# ina_board.net
KiCad netlist of a schematic drawn in EAGLE
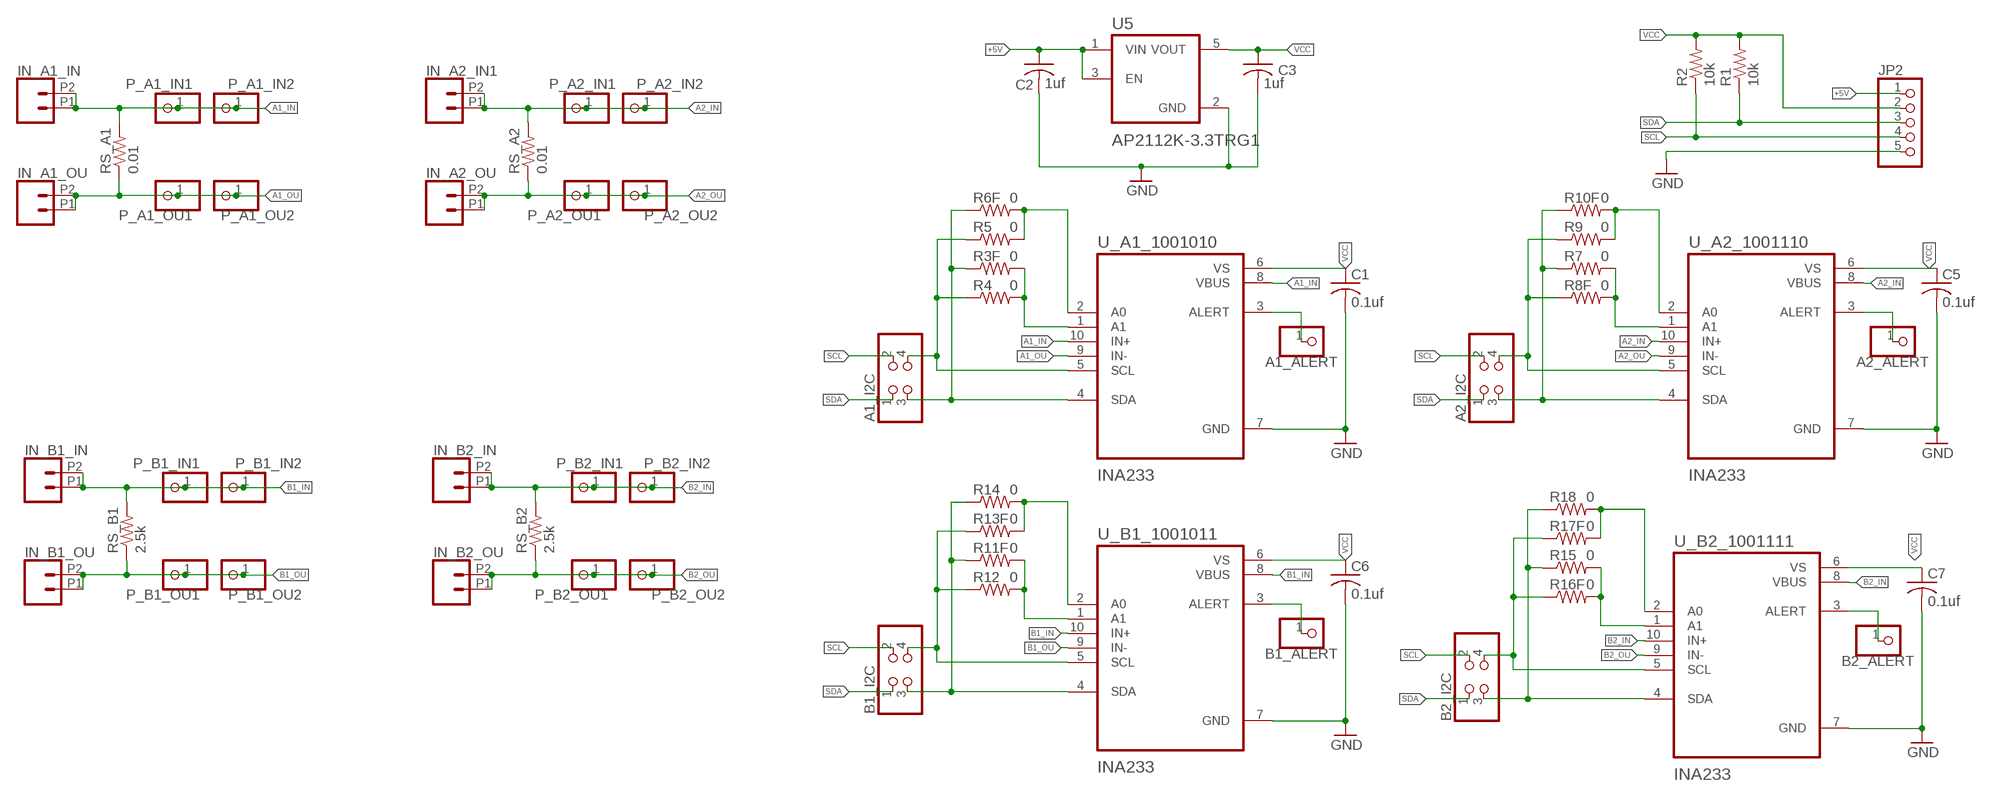
[diagram p0: schematic, sheet 1]

(export (version "E")
  (design (tool "Eeschema 10.0.6"))
  (components
    (comp (ref "A1_ALERT")
      (value "PINHD-1X1")
      (footprint "eagle-import:1X01")
      (libsource (lib "eagle-import") (part "pinhead_325_PINHD-1X1"))
    )
    (comp (ref "A1_I2C")
      (value "PINHD-2X2")
      (footprint "eagle-import:2X02")
      (libsource (lib "eagle-import") (part "PINHD-2X2"))
    )
    (comp (ref "A2_ALERT")
      (value "PINHD-1X1")
      (footprint "eagle-import:1X01")
      (libsource (lib "eagle-import") (part "pinhead_325_PINHD-1X1"))
    )
    (comp (ref "A2_I2C")
      (value "PINHD-2X2")
      (footprint "eagle-import:2X02")
      (libsource (lib "eagle-import") (part "PINHD-2X2"))
    )
    (comp (ref "B1_ALERT")
      (value "PINHD-1X1")
      (footprint "eagle-import:1X01")
      (libsource (lib "eagle-import") (part "pinhead_325_PINHD-1X1"))
    )
    (comp (ref "B1_I2C")
      (value "PINHD-2X2")
      (footprint "eagle-import:2X02")
      (libsource (lib "eagle-import") (part "PINHD-2X2"))
    )
    (comp (ref "B2_ALERT")
      (value "PINHD-1X1")
      (footprint "eagle-import:1X01")
      (libsource (lib "eagle-import") (part "pinhead_325_PINHD-1X1"))
    )
    (comp (ref "B2_I2C")
      (value "PINHD-2X2")
      (footprint "eagle-import:2X02")
      (libsource (lib "eagle-import") (part "PINHD-2X2"))
    )
    (comp (ref "C1")
      (value "0.1uf")
      (footprint "eagle-import:C0805")
      (libsource (lib "eagle-import") (part "C-USC0805"))
    )
    (comp (ref "C2")
      (value "1uf")
      (footprint "eagle-import:C1210")
      (libsource (lib "eagle-import") (part "C-USC1210"))
    )
    (comp (ref "C3")
      (value "1uf")
      (footprint "eagle-import:C1210")
      (libsource (lib "eagle-import") (part "C-USC1210"))
    )
    (comp (ref "C5")
      (value "0.1uf")
      (footprint "eagle-import:C0805")
      (libsource (lib "eagle-import") (part "C-USC0805"))
    )
    (comp (ref "C6")
      (value "0.1uf")
      (footprint "eagle-import:C0805")
      (libsource (lib "eagle-import") (part "C-USC0805"))
    )
    (comp (ref "C7")
      (value "0.1uf")
      (footprint "eagle-import:C0805")
      (libsource (lib "eagle-import") (part "C-USC0805"))
    )
    (comp (ref "IN_A1_IN")
      (value "CONN_022.54MM_SCREWTERM")
      (footprint "eagle-import:1X02_2.54_SCREWTERM")
      (libsource (lib "eagle-import") (part "CONN_022.54MM_SCREWTERM"))
    )
    (comp (ref "IN_A1_OU")
      (value "CONN_022.54MM_SCREWTERM")
      (footprint "eagle-import:1X02_2.54_SCREWTERM")
      (libsource (lib "eagle-import") (part "CONN_022.54MM_SCREWTERM"))
    )
    (comp (ref "IN_A2_IN1")
      (value "CONN_022.54MM_SCREWTERM")
      (footprint "eagle-import:1X02_2.54_SCREWTERM")
      (libsource (lib "eagle-import") (part "CONN_022.54MM_SCREWTERM"))
    )
    (comp (ref "IN_A2_OU")
      (value "CONN_022.54MM_SCREWTERM")
      (footprint "eagle-import:1X02_2.54_SCREWTERM")
      (libsource (lib "eagle-import") (part "CONN_022.54MM_SCREWTERM"))
    )
    (comp (ref "IN_B1_IN")
      (value "CONN_022.54MM_SCREWTERM")
      (footprint "eagle-import:1X02_2.54_SCREWTERM")
      (libsource (lib "eagle-import") (part "CONN_022.54MM_SCREWTERM"))
    )
    (comp (ref "IN_B1_OU")
      (value "CONN_022.54MM_SCREWTERM")
      (footprint "eagle-import:1X02_2.54_SCREWTERM")
      (libsource (lib "eagle-import") (part "CONN_022.54MM_SCREWTERM"))
    )
    (comp (ref "IN_B2_IN")
      (value "CONN_022.54MM_SCREWTERM")
      (footprint "eagle-import:1X02_2.54_SCREWTERM")
      (libsource (lib "eagle-import") (part "CONN_022.54MM_SCREWTERM"))
    )
    (comp (ref "IN_B2_OU")
      (value "CONN_022.54MM_SCREWTERM")
      (footprint "eagle-import:1X02_2.54_SCREWTERM")
      (libsource (lib "eagle-import") (part "CONN_022.54MM_SCREWTERM"))
    )
    (comp (ref "JP2")
      (value "PINHD-1X5")
      (footprint "eagle-import:1X05")
      (libsource (lib "eagle-import") (part "PINHD-1X5"))
    )
    (comp (ref "P_A1_IN1")
      (value "PINHD-1X1")
      (footprint "eagle-import:1X01")
      (libsource (lib "eagle-import") (part "PINHD-1X1"))
    )
    (comp (ref "P_A1_IN2")
      (value "PINHD-1X1")
      (footprint "eagle-import:1X01")
      (libsource (lib "eagle-import") (part "PINHD-1X1"))
    )
    (comp (ref "P_A1_OU1")
      (value "PINHD-1X1")
      (footprint "eagle-import:1X01")
      (libsource (lib "eagle-import") (part "PINHD-1X1"))
    )
    (comp (ref "P_A1_OU2")
      (value "PINHD-1X1")
      (footprint "eagle-import:1X01")
      (libsource (lib "eagle-import") (part "PINHD-1X1"))
    )
    (comp (ref "P_A2_IN1")
      (value "PINHD-1X1")
      (footprint "eagle-import:1X01")
      (libsource (lib "eagle-import") (part "PINHD-1X1"))
    )
    (comp (ref "P_A2_IN2")
      (value "PINHD-1X1")
      (footprint "eagle-import:1X01")
      (libsource (lib "eagle-import") (part "PINHD-1X1"))
    )
    (comp (ref "P_A2_OU1")
      (value "PINHD-1X1")
      (footprint "eagle-import:1X01")
      (libsource (lib "eagle-import") (part "PINHD-1X1"))
    )
    (comp (ref "P_A2_OU2")
      (value "PINHD-1X1")
      (footprint "eagle-import:1X01")
      (libsource (lib "eagle-import") (part "PINHD-1X1"))
    )
    (comp (ref "P_B1_IN1")
      (value "PINHD-1X1")
      (footprint "eagle-import:1X01")
      (libsource (lib "eagle-import") (part "PINHD-1X1"))
    )
    (comp (ref "P_B1_IN2")
      (value "PINHD-1X1")
      (footprint "eagle-import:1X01")
      (libsource (lib "eagle-import") (part "PINHD-1X1"))
    )
    (comp (ref "P_B1_OU1")
      (value "PINHD-1X1")
      (footprint "eagle-import:1X01")
      (libsource (lib "eagle-import") (part "PINHD-1X1"))
    )
    (comp (ref "P_B1_OU2")
      (value "PINHD-1X1")
      (footprint "eagle-import:1X01")
      (libsource (lib "eagle-import") (part "PINHD-1X1"))
    )
    (comp (ref "P_B2_IN1")
      (value "PINHD-1X1")
      (footprint "eagle-import:1X01")
      (libsource (lib "eagle-import") (part "PINHD-1X1"))
    )
    (comp (ref "P_B2_IN2")
      (value "PINHD-1X1")
      (footprint "eagle-import:1X01")
      (libsource (lib "eagle-import") (part "PINHD-1X1"))
    )
    (comp (ref "P_B2_OU1")
      (value "PINHD-1X1")
      (footprint "eagle-import:1X01")
      (libsource (lib "eagle-import") (part "PINHD-1X1"))
    )
    (comp (ref "P_B2_OU2")
      (value "PINHD-1X1")
      (footprint "eagle-import:1X01")
      (libsource (lib "eagle-import") (part "PINHD-1X1"))
    )
    (comp (ref "R1")
      (value "10k")
      (footprint "eagle-import:R0805")
      (libsource (lib "eagle-import") (part "R-US_R0805"))
    )
    (comp (ref "R2")
      (value "10k")
      (footprint "eagle-import:R0805")
      (libsource (lib "eagle-import") (part "R-US_R0805"))
    )
    (comp (ref "R3F")
      (value "0")
      (footprint "eagle-import:R0805")
      (libsource (lib "eagle-import") (part "R-US_R0805"))
    )
    (comp (ref "R4")
      (value "0")
      (footprint "eagle-import:R0805")
      (libsource (lib "eagle-import") (part "R-US_R0805"))
    )
    (comp (ref "R5")
      (value "0")
      (footprint "eagle-import:R0805")
      (libsource (lib "eagle-import") (part "R-US_R0805"))
    )
    (comp (ref "R6F")
      (value "0")
      (footprint "eagle-import:R0805")
      (libsource (lib "eagle-import") (part "R-US_R0805"))
    )
    (comp (ref "R7")
      (value "0")
      (footprint "eagle-import:R0805")
      (libsource (lib "eagle-import") (part "R-US_R0805"))
    )
    (comp (ref "R8F")
      (value "0")
      (footprint "eagle-import:R0805")
      (libsource (lib "eagle-import") (part "R-US_R0805"))
    )
    (comp (ref "R9")
      (value "0")
      (footprint "eagle-import:R0805")
      (libsource (lib "eagle-import") (part "R-US_R0805"))
    )
    (comp (ref "R10F")
      (value "0")
      (footprint "eagle-import:R0805")
      (libsource (lib "eagle-import") (part "R-US_R0805"))
    )
    (comp (ref "R11F")
      (value "0")
      (footprint "eagle-import:R0805")
      (libsource (lib "eagle-import") (part "R-US_R0805"))
    )
    (comp (ref "R12")
      (value "0")
      (footprint "eagle-import:R0805")
      (libsource (lib "eagle-import") (part "R-US_R0805"))
    )
    (comp (ref "R13F")
      (value "0")
      (footprint "eagle-import:R0805")
      (libsource (lib "eagle-import") (part "R-US_R0805"))
    )
    (comp (ref "R14")
      (value "0")
      (footprint "eagle-import:R0805")
      (libsource (lib "eagle-import") (part "R-US_R0805"))
    )
    (comp (ref "R15")
      (value "0")
      (footprint "eagle-import:R0805")
      (libsource (lib "eagle-import") (part "R-US_R0805"))
    )
    (comp (ref "R16F")
      (value "0")
      (footprint "eagle-import:R0805")
      (libsource (lib "eagle-import") (part "R-US_R0805"))
    )
    (comp (ref "R17F")
      (value "0")
      (footprint "eagle-import:R0805")
      (libsource (lib "eagle-import") (part "R-US_R0805"))
    )
    (comp (ref "R18")
      (value "0")
      (footprint "eagle-import:R0805")
      (libsource (lib "eagle-import") (part "R-US_R0805"))
    )
    (comp (ref "RS_A1")
      (value "0.01")
      (footprint "eagle-import:R2512")
      (libsource (lib "eagle-import") (part "R-US_R2512"))
    )
    (comp (ref "RS_A2")
      (value "0.01")
      (footprint "eagle-import:R2512")
      (libsource (lib "eagle-import") (part "R-US_R2512"))
    )
    (comp (ref "RS_B1")
      (value "2.5k")
      (footprint "eagle-import:R0805")
      (libsource (lib "eagle-import") (part "R-US_R0805"))
    )
    (comp (ref "RS_B2")
      (value "2.5k")
      (footprint "eagle-import:R0805")
      (libsource (lib "eagle-import") (part "R-US_R0805"))
    )
    (comp (ref "U5")
      (value "AP2112K-3.3TRG1")
      (footprint "eagle-import:SOT95P285X140-5N")
      (fields (field (name "MF") "Diodes Inc."))
      (libsource (lib "eagle-import") (part "AP2112K-3.3TRG1"))
    )
    (comp (ref "U_A1_1001010")
      (value "INA233")
      (footprint "eagle-import:SOP50P490X110-10N")
      (fields (field (name "MF") "Texas Instruments") (field (name "MP") "INA226AIDGST"))
      (libsource (lib "eagle-import") (part "INA226AIDGST"))
    )
    (comp (ref "U_A2_1001110")
      (value "INA233")
      (footprint "eagle-import:SOP50P490X110-10N")
      (fields (field (name "MF") "Texas Instruments") (field (name "MP") "INA226AIDGST"))
      (libsource (lib "eagle-import") (part "INA226AIDGST"))
    )
    (comp (ref "U_B1_1001011")
      (value "INA233")
      (footprint "eagle-import:SOP50P490X110-10N")
      (fields (field (name "MF") "Texas Instruments") (field (name "MP") "INA226AIDGST"))
      (libsource (lib "eagle-import") (part "INA226AIDGST"))
    )
    (comp (ref "U_B2_1001111")
      (value "INA233")
      (footprint "eagle-import:SOP50P490X110-10N")
      (fields (field (name "MF") "Texas Instruments") (field (name "MP") "INA226AIDGST"))
      (libsource (lib "eagle-import") (part "INA226AIDGST"))
    )
  )
  (nets
    (net (code "1") (name "+5V") (class "Default")
      (node (ref "C2") (pin "1") (pinfunction "1_1") (pintype "passive"))
      (node (ref "JP2") (pin "1") (pinfunction "1_1") (pintype "passive"))
      (node (ref "U5") (pin "1") (pinfunction "VIN_1") (pintype "power_in"))
      (node (ref "U5") (pin "3") (pinfunction "EN_3") (pintype "input"))
    )
    (net (code "2") (name "A1_IN") (class "Default")
      (node (ref "IN_A1_IN") (pin "P1") (pinfunction "1_P1") (pintype "passive"))
      (node (ref "IN_A1_IN") (pin "P2") (pinfunction "2_P2") (pintype "passive"))
      (node (ref "P_A1_IN1") (pin "1") (pinfunction "1_1") (pintype "passive"))
      (node (ref "P_A1_IN2") (pin "1") (pinfunction "1_1") (pintype "passive"))
      (node (ref "RS_A1") (pin "2") (pinfunction "2_2") (pintype "passive"))
      (node (ref "U_A1_1001010") (pin "10") (pinfunction "IN+_10") (pintype "input"))
      (node (ref "U_A1_1001010") (pin "8") (pinfunction "VBUS_8") (pintype "power_in"))
    )
    (net (code "3") (name "A1_OU") (class "Default")
      (node (ref "IN_A1_OU") (pin "P1") (pinfunction "1_P1") (pintype "passive"))
      (node (ref "IN_A1_OU") (pin "P2") (pinfunction "2_P2") (pintype "passive"))
      (node (ref "P_A1_OU1") (pin "1") (pinfunction "1_1") (pintype "passive"))
      (node (ref "P_A1_OU2") (pin "1") (pinfunction "1_1") (pintype "passive"))
      (node (ref "RS_A1") (pin "1") (pinfunction "1_1") (pintype "passive"))
      (node (ref "U_A1_1001010") (pin "9") (pinfunction "IN-_9") (pintype "input"))
    )
    (net (code "4") (name "A2_IN") (class "Default")
      (node (ref "IN_A2_IN1") (pin "P1") (pinfunction "1_P1") (pintype "passive"))
      (node (ref "IN_A2_IN1") (pin "P2") (pinfunction "2_P2") (pintype "passive"))
      (node (ref "P_A2_IN1") (pin "1") (pinfunction "1_1") (pintype "passive"))
      (node (ref "P_A2_IN2") (pin "1") (pinfunction "1_1") (pintype "passive"))
      (node (ref "RS_A2") (pin "2") (pinfunction "2_2") (pintype "passive"))
      (node (ref "U_A2_1001110") (pin "10") (pinfunction "IN+_10") (pintype "input"))
      (node (ref "U_A2_1001110") (pin "8") (pinfunction "VBUS_8") (pintype "power_in"))
    )
    (net (code "5") (name "A2_OU") (class "Default")
      (node (ref "IN_A2_OU") (pin "P1") (pinfunction "1_P1") (pintype "passive"))
      (node (ref "IN_A2_OU") (pin "P2") (pinfunction "2_P2") (pintype "passive"))
      (node (ref "P_A2_OU1") (pin "1") (pinfunction "1_1") (pintype "passive"))
      (node (ref "P_A2_OU2") (pin "1") (pinfunction "1_1") (pintype "passive"))
      (node (ref "RS_A2") (pin "1") (pinfunction "1_1") (pintype "passive"))
      (node (ref "U_A2_1001110") (pin "9") (pinfunction "IN-_9") (pintype "input"))
    )
    (net (code "6") (name "B1_IN") (class "Default")
      (node (ref "IN_B1_IN") (pin "P1") (pinfunction "1_P1") (pintype "passive"))
      (node (ref "IN_B1_IN") (pin "P2") (pinfunction "2_P2") (pintype "passive"))
      (node (ref "P_B1_IN1") (pin "1") (pinfunction "1_1") (pintype "passive"))
      (node (ref "P_B1_IN2") (pin "1") (pinfunction "1_1") (pintype "passive"))
      (node (ref "RS_B1") (pin "2") (pinfunction "2_2") (pintype "passive"))
      (node (ref "U_B1_1001011") (pin "10") (pinfunction "IN+_10") (pintype "input"))
      (node (ref "U_B1_1001011") (pin "8") (pinfunction "VBUS_8") (pintype "power_in"))
    )
    (net (code "7") (name "B1_OU") (class "Default")
      (node (ref "IN_B1_OU") (pin "P1") (pinfunction "1_P1") (pintype "passive"))
      (node (ref "IN_B1_OU") (pin "P2") (pinfunction "2_P2") (pintype "passive"))
      (node (ref "P_B1_OU1") (pin "1") (pinfunction "1_1") (pintype "passive"))
      (node (ref "P_B1_OU2") (pin "1") (pinfunction "1_1") (pintype "passive"))
      (node (ref "RS_B1") (pin "1") (pinfunction "1_1") (pintype "passive"))
      (node (ref "U_B1_1001011") (pin "9") (pinfunction "IN-_9") (pintype "input"))
    )
    (net (code "8") (name "B2_IN") (class "Default")
      (node (ref "IN_B2_IN") (pin "P1") (pinfunction "1_P1") (pintype "passive"))
      (node (ref "IN_B2_IN") (pin "P2") (pinfunction "2_P2") (pintype "passive"))
      (node (ref "P_B2_IN1") (pin "1") (pinfunction "1_1") (pintype "passive"))
      (node (ref "P_B2_IN2") (pin "1") (pinfunction "1_1") (pintype "passive"))
      (node (ref "RS_B2") (pin "2") (pinfunction "2_2") (pintype "passive"))
      (node (ref "U_B2_1001111") (pin "10") (pinfunction "IN+_10") (pintype "input"))
      (node (ref "U_B2_1001111") (pin "8") (pinfunction "VBUS_8") (pintype "power_in"))
    )
    (net (code "9") (name "B2_OU") (class "Default")
      (node (ref "IN_B2_OU") (pin "P1") (pinfunction "1_P1") (pintype "passive"))
      (node (ref "IN_B2_OU") (pin "P2") (pinfunction "2_P2") (pintype "passive"))
      (node (ref "P_B2_OU1") (pin "1") (pinfunction "1_1") (pintype "passive"))
      (node (ref "P_B2_OU2") (pin "1") (pinfunction "1_1") (pintype "passive"))
      (node (ref "RS_B2") (pin "1") (pinfunction "1_1") (pintype "passive"))
      (node (ref "U_B2_1001111") (pin "9") (pinfunction "IN-_9") (pintype "input"))
    )
    (net (code "10") (name "GND") (class "Default")
      (node (ref "C1") (pin "2") (pinfunction "2_2") (pintype "passive"))
      (node (ref "C2") (pin "2") (pinfunction "2_2") (pintype "passive"))
      (node (ref "C3") (pin "2") (pinfunction "2_2") (pintype "passive"))
      (node (ref "C5") (pin "2") (pinfunction "2_2") (pintype "passive"))
      (node (ref "C6") (pin "2") (pinfunction "2_2") (pintype "passive"))
      (node (ref "C7") (pin "2") (pinfunction "2_2") (pintype "passive"))
      (node (ref "JP2") (pin "5") (pinfunction "5_5") (pintype "passive"))
      (node (ref "U5") (pin "2") (pinfunction "GND_2") (pintype "power_in"))
      (node (ref "U_A1_1001010") (pin "7") (pinfunction "GND_7") (pintype "power_in"))
      (node (ref "U_A2_1001110") (pin "7") (pinfunction "GND_7") (pintype "power_in"))
      (node (ref "U_B1_1001011") (pin "7") (pinfunction "GND_7") (pintype "power_in"))
      (node (ref "U_B2_1001111") (pin "7") (pinfunction "GND_7") (pintype "power_in"))
    )
    (net (code "11") (name "Net-(U_A1_1001010-A0)") (class "Default")
      (node (ref "R5") (pin "2") (pinfunction "2_2") (pintype "passive"))
      (node (ref "R6F") (pin "2") (pinfunction "2_2") (pintype "passive"))
      (node (ref "U_A1_1001010") (pin "2") (pinfunction "A0_2") (pintype "input"))
    )
    (net (code "12") (name "Net-(U_A1_1001010-A1)") (class "Default")
      (node (ref "R3F") (pin "2") (pinfunction "2_2") (pintype "passive"))
      (node (ref "R4") (pin "2") (pinfunction "2_2") (pintype "passive"))
      (node (ref "U_A1_1001010") (pin "1") (pinfunction "A1_1") (pintype "input"))
    )
    (net (code "13") (name "Net-(U_A1_1001010-ALERT)") (class "Default")
      (node (ref "A1_ALERT") (pin "1") (pinfunction "1_1") (pintype "passive"))
      (node (ref "U_A1_1001010") (pin "3") (pinfunction "ALERT_3") (pintype "output"))
    )
    (net (code "14") (name "Net-(U_A1_1001010-SCL)") (class "Default")
      (node (ref "A1_I2C") (pin "4") (pinfunction "4_4") (pintype "passive"))
      (node (ref "R4") (pin "1") (pinfunction "1_1") (pintype "passive"))
      (node (ref "R5") (pin "1") (pinfunction "1_1") (pintype "passive"))
      (node (ref "U_A1_1001010") (pin "5") (pinfunction "SCL_5") (pintype "input"))
    )
    (net (code "15") (name "Net-(U_A1_1001010-SDA)") (class "Default")
      (node (ref "A1_I2C") (pin "3") (pinfunction "3_3") (pintype "passive"))
      (node (ref "R3F") (pin "1") (pinfunction "1_1") (pintype "passive"))
      (node (ref "R6F") (pin "1") (pinfunction "1_1") (pintype "passive"))
      (node (ref "U_A1_1001010") (pin "4") (pinfunction "SDA_4") (pintype "bidirectional"))
    )
    (net (code "16") (name "Net-(U_A2_1001110-A0)") (class "Default")
      (node (ref "R10F") (pin "2") (pinfunction "2_2") (pintype "passive"))
      (node (ref "R9") (pin "2") (pinfunction "2_2") (pintype "passive"))
      (node (ref "U_A2_1001110") (pin "2") (pinfunction "A0_2") (pintype "input"))
    )
    (net (code "17") (name "Net-(U_A2_1001110-A1)") (class "Default")
      (node (ref "R7") (pin "2") (pinfunction "2_2") (pintype "passive"))
      (node (ref "R8F") (pin "2") (pinfunction "2_2") (pintype "passive"))
      (node (ref "U_A2_1001110") (pin "1") (pinfunction "A1_1") (pintype "input"))
    )
    (net (code "18") (name "Net-(U_A2_1001110-ALERT)") (class "Default")
      (node (ref "A2_ALERT") (pin "1") (pinfunction "1_1") (pintype "passive"))
      (node (ref "U_A2_1001110") (pin "3") (pinfunction "ALERT_3") (pintype "output"))
    )
    (net (code "19") (name "Net-(U_A2_1001110-SCL)") (class "Default")
      (node (ref "A2_I2C") (pin "4") (pinfunction "4_4") (pintype "passive"))
      (node (ref "R8F") (pin "1") (pinfunction "1_1") (pintype "passive"))
      (node (ref "R9") (pin "1") (pinfunction "1_1") (pintype "passive"))
      (node (ref "U_A2_1001110") (pin "5") (pinfunction "SCL_5") (pintype "input"))
    )
    (net (code "20") (name "Net-(U_A2_1001110-SDA)") (class "Default")
      (node (ref "A2_I2C") (pin "3") (pinfunction "3_3") (pintype "passive"))
      (node (ref "R10F") (pin "1") (pinfunction "1_1") (pintype "passive"))
      (node (ref "R7") (pin "1") (pinfunction "1_1") (pintype "passive"))
      (node (ref "U_A2_1001110") (pin "4") (pinfunction "SDA_4") (pintype "bidirectional"))
    )
    (net (code "21") (name "Net-(U_B1_1001011-A0)") (class "Default")
      (node (ref "R13F") (pin "2") (pinfunction "2_2") (pintype "passive"))
      (node (ref "R14") (pin "2") (pinfunction "2_2") (pintype "passive"))
      (node (ref "U_B1_1001011") (pin "2") (pinfunction "A0_2") (pintype "input"))
    )
    (net (code "22") (name "Net-(U_B1_1001011-A1)") (class "Default")
      (node (ref "R11F") (pin "2") (pinfunction "2_2") (pintype "passive"))
      (node (ref "R12") (pin "2") (pinfunction "2_2") (pintype "passive"))
      (node (ref "U_B1_1001011") (pin "1") (pinfunction "A1_1") (pintype "input"))
    )
    (net (code "23") (name "Net-(U_B1_1001011-ALERT)") (class "Default")
      (node (ref "B1_ALERT") (pin "1") (pinfunction "1_1") (pintype "passive"))
      (node (ref "U_B1_1001011") (pin "3") (pinfunction "ALERT_3") (pintype "output"))
    )
    (net (code "24") (name "Net-(U_B1_1001011-SCL)") (class "Default")
      (node (ref "B1_I2C") (pin "4") (pinfunction "4_4") (pintype "passive"))
      (node (ref "R12") (pin "1") (pinfunction "1_1") (pintype "passive"))
      (node (ref "R13F") (pin "1") (pinfunction "1_1") (pintype "passive"))
      (node (ref "U_B1_1001011") (pin "5") (pinfunction "SCL_5") (pintype "input"))
    )
    (net (code "25") (name "Net-(U_B1_1001011-SDA)") (class "Default")
      (node (ref "B1_I2C") (pin "3") (pinfunction "3_3") (pintype "passive"))
      (node (ref "R11F") (pin "1") (pinfunction "1_1") (pintype "passive"))
      (node (ref "R14") (pin "1") (pinfunction "1_1") (pintype "passive"))
      (node (ref "U_B1_1001011") (pin "4") (pinfunction "SDA_4") (pintype "bidirectional"))
    )
    (net (code "26") (name "Net-(U_B2_1001111-A0)") (class "Default")
      (node (ref "R17F") (pin "2") (pinfunction "2_2") (pintype "passive"))
      (node (ref "R18") (pin "2") (pinfunction "2_2") (pintype "passive"))
      (node (ref "U_B2_1001111") (pin "2") (pinfunction "A0_2") (pintype "input"))
    )
    (net (code "27") (name "Net-(U_B2_1001111-A1)") (class "Default")
      (node (ref "R15") (pin "2") (pinfunction "2_2") (pintype "passive"))
      (node (ref "R16F") (pin "2") (pinfunction "2_2") (pintype "passive"))
      (node (ref "U_B2_1001111") (pin "1") (pinfunction "A1_1") (pintype "input"))
    )
    (net (code "28") (name "Net-(U_B2_1001111-ALERT)") (class "Default")
      (node (ref "B2_ALERT") (pin "1") (pinfunction "1_1") (pintype "passive"))
      (node (ref "U_B2_1001111") (pin "3") (pinfunction "ALERT_3") (pintype "output"))
    )
    (net (code "29") (name "Net-(U_B2_1001111-SCL)") (class "Default")
      (node (ref "B2_I2C") (pin "4") (pinfunction "4_4") (pintype "passive"))
      (node (ref "R16F") (pin "1") (pinfunction "1_1") (pintype "passive"))
      (node (ref "R17F") (pin "1") (pinfunction "1_1") (pintype "passive"))
      (node (ref "U_B2_1001111") (pin "5") (pinfunction "SCL_5") (pintype "input"))
    )
    (net (code "30") (name "Net-(U_B2_1001111-SDA)") (class "Default")
      (node (ref "B2_I2C") (pin "3") (pinfunction "3_3") (pintype "passive"))
      (node (ref "R15") (pin "1") (pinfunction "1_1") (pintype "passive"))
      (node (ref "R18") (pin "1") (pinfunction "1_1") (pintype "passive"))
      (node (ref "U_B2_1001111") (pin "4") (pinfunction "SDA_4") (pintype "bidirectional"))
    )
    (net (code "31") (name "SCL") (class "Default")
      (node (ref "A1_I2C") (pin "2") (pinfunction "2_2") (pintype "passive"))
      (node (ref "A2_I2C") (pin "2") (pinfunction "2_2") (pintype "passive"))
      (node (ref "B1_I2C") (pin "2") (pinfunction "2_2") (pintype "passive"))
      (node (ref "B2_I2C") (pin "2") (pinfunction "2_2") (pintype "passive"))
      (node (ref "JP2") (pin "4") (pinfunction "4_4") (pintype "passive"))
      (node (ref "R2") (pin "1") (pinfunction "1_1") (pintype "passive"))
    )
    (net (code "32") (name "SDA") (class "Default")
      (node (ref "A1_I2C") (pin "1") (pinfunction "1_1") (pintype "passive"))
      (node (ref "A2_I2C") (pin "1") (pinfunction "1_1") (pintype "passive"))
      (node (ref "B1_I2C") (pin "1") (pinfunction "1_1") (pintype "passive"))
      (node (ref "B2_I2C") (pin "1") (pinfunction "1_1") (pintype "passive"))
      (node (ref "JP2") (pin "3") (pinfunction "3_3") (pintype "passive"))
      (node (ref "R1") (pin "1") (pinfunction "1_1") (pintype "passive"))
    )
    (net (code "33") (name "VCC") (class "Default")
      (node (ref "C1") (pin "1") (pinfunction "1_1") (pintype "passive"))
      (node (ref "C3") (pin "1") (pinfunction "1_1") (pintype "passive"))
      (node (ref "C5") (pin "1") (pinfunction "1_1") (pintype "passive"))
      (node (ref "C6") (pin "1") (pinfunction "1_1") (pintype "passive"))
      (node (ref "C7") (pin "1") (pinfunction "1_1") (pintype "passive"))
      (node (ref "JP2") (pin "2") (pinfunction "2_2") (pintype "passive"))
      (node (ref "R1") (pin "2") (pinfunction "2_2") (pintype "passive"))
      (node (ref "R2") (pin "2") (pinfunction "2_2") (pintype "passive"))
      (node (ref "U5") (pin "5") (pinfunction "VOUT_5") (pintype "power_in"))
      (node (ref "U_A1_1001010") (pin "6") (pinfunction "VS_6") (pintype "power_in"))
      (node (ref "U_A2_1001110") (pin "6") (pinfunction "VS_6") (pintype "power_in"))
      (node (ref "U_B1_1001011") (pin "6") (pinfunction "VS_6") (pintype "power_in"))
      (node (ref "U_B2_1001111") (pin "6") (pinfunction "VS_6") (pintype "power_in"))
    )
  )
)
